# zeta2rework_lw_v36_ripup.net
KiCad netlist of a schematic drawn in EAGLE
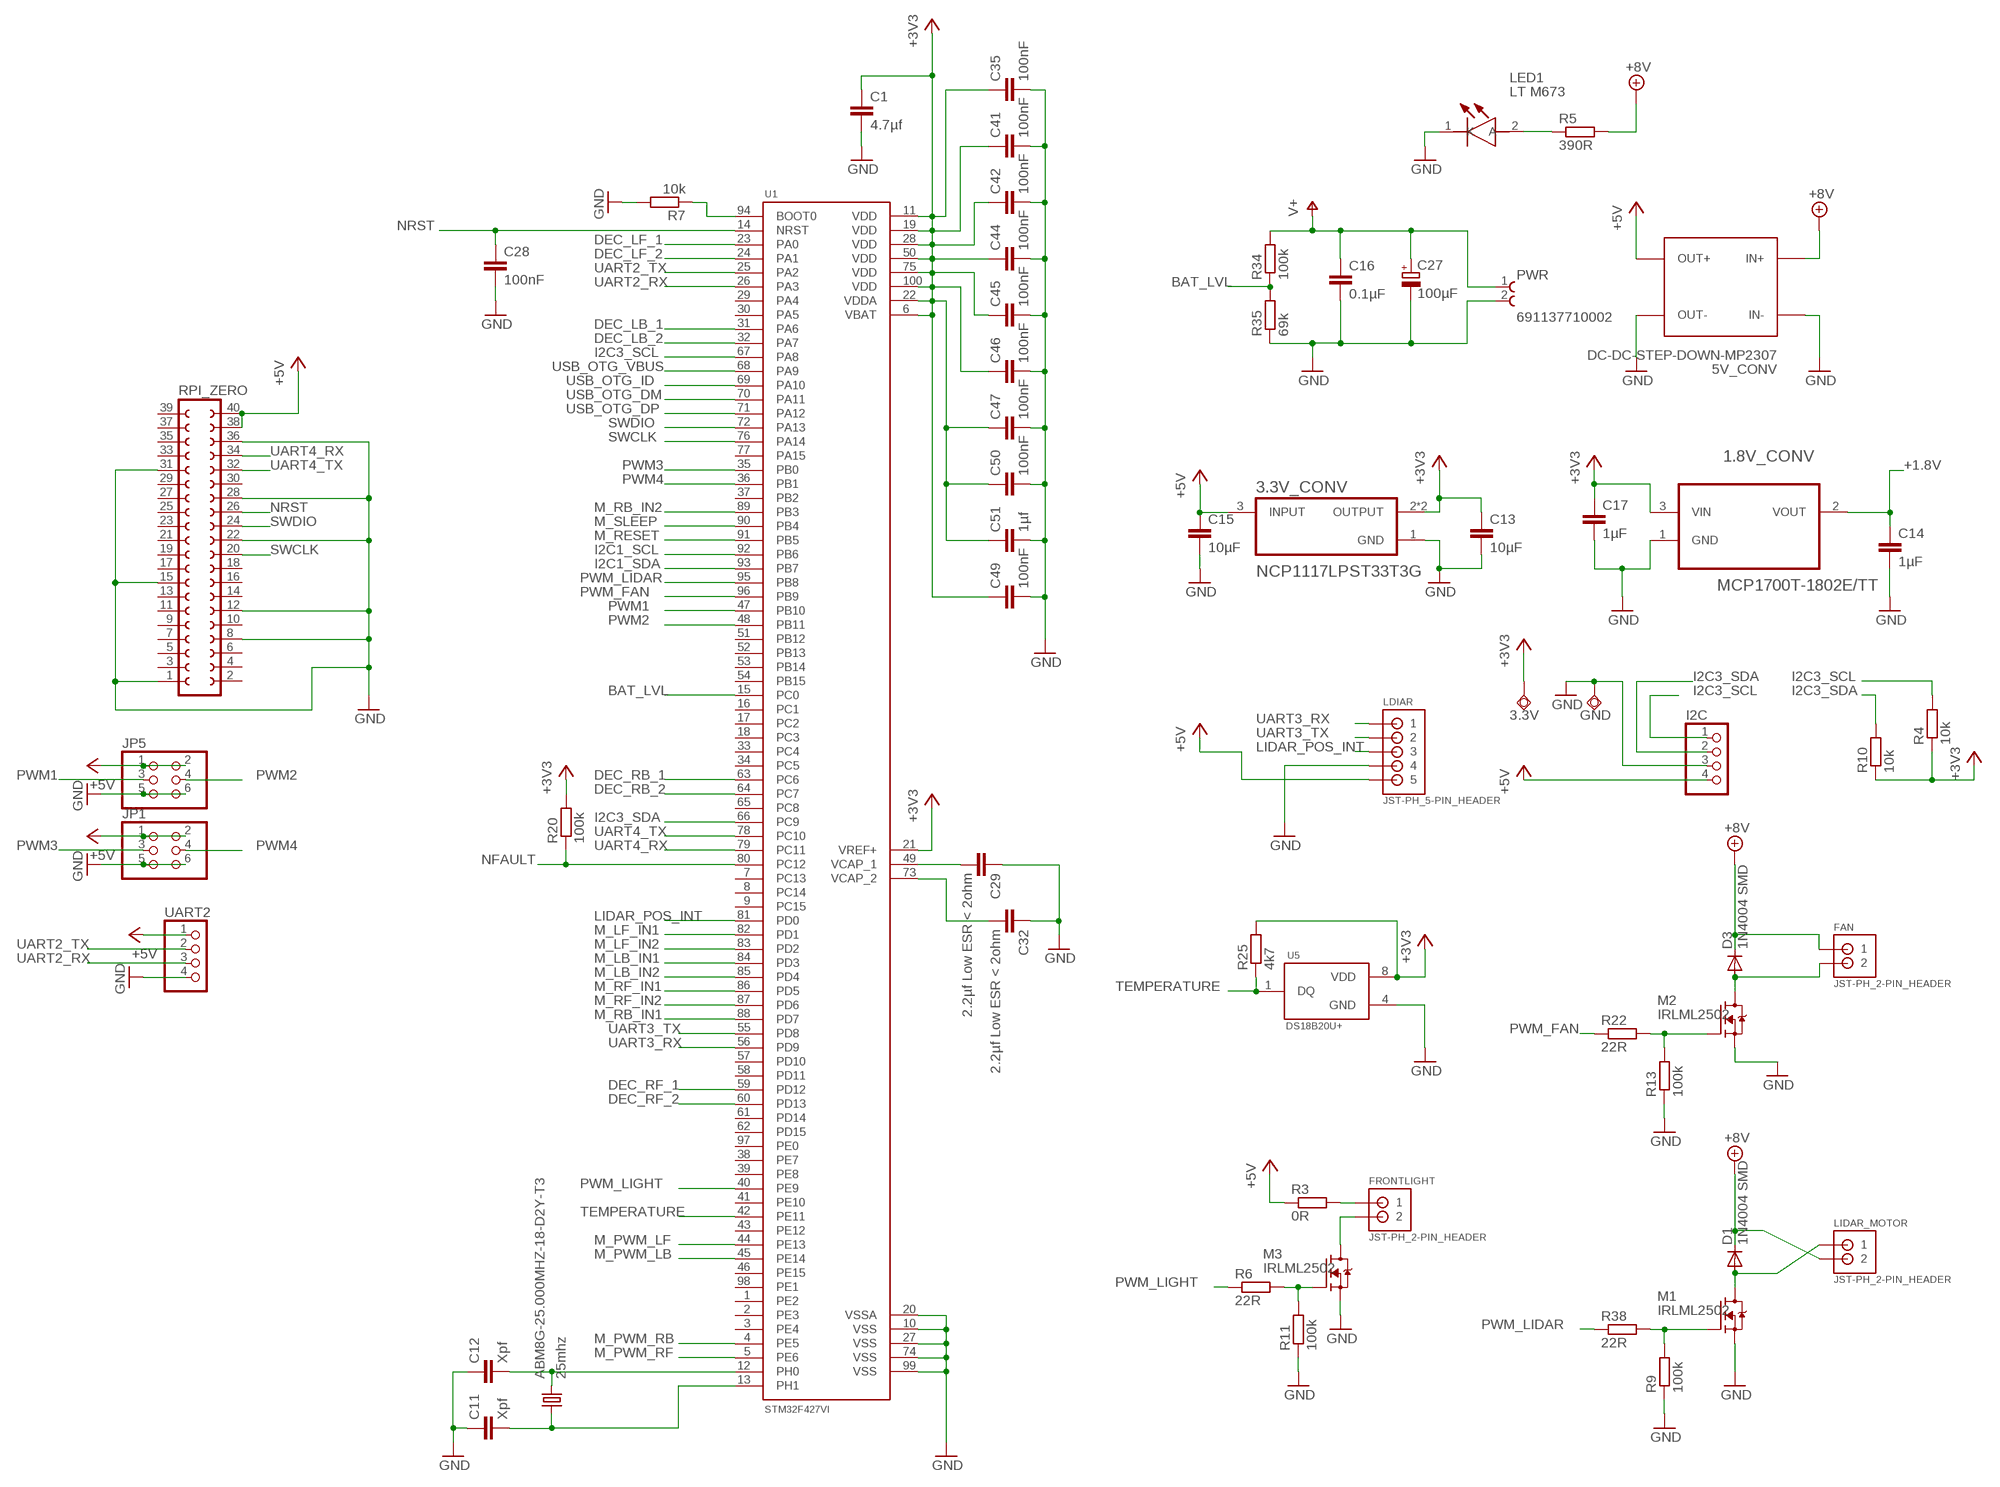
[diagram p0: schematic, sheet 1, part 1 of 2]
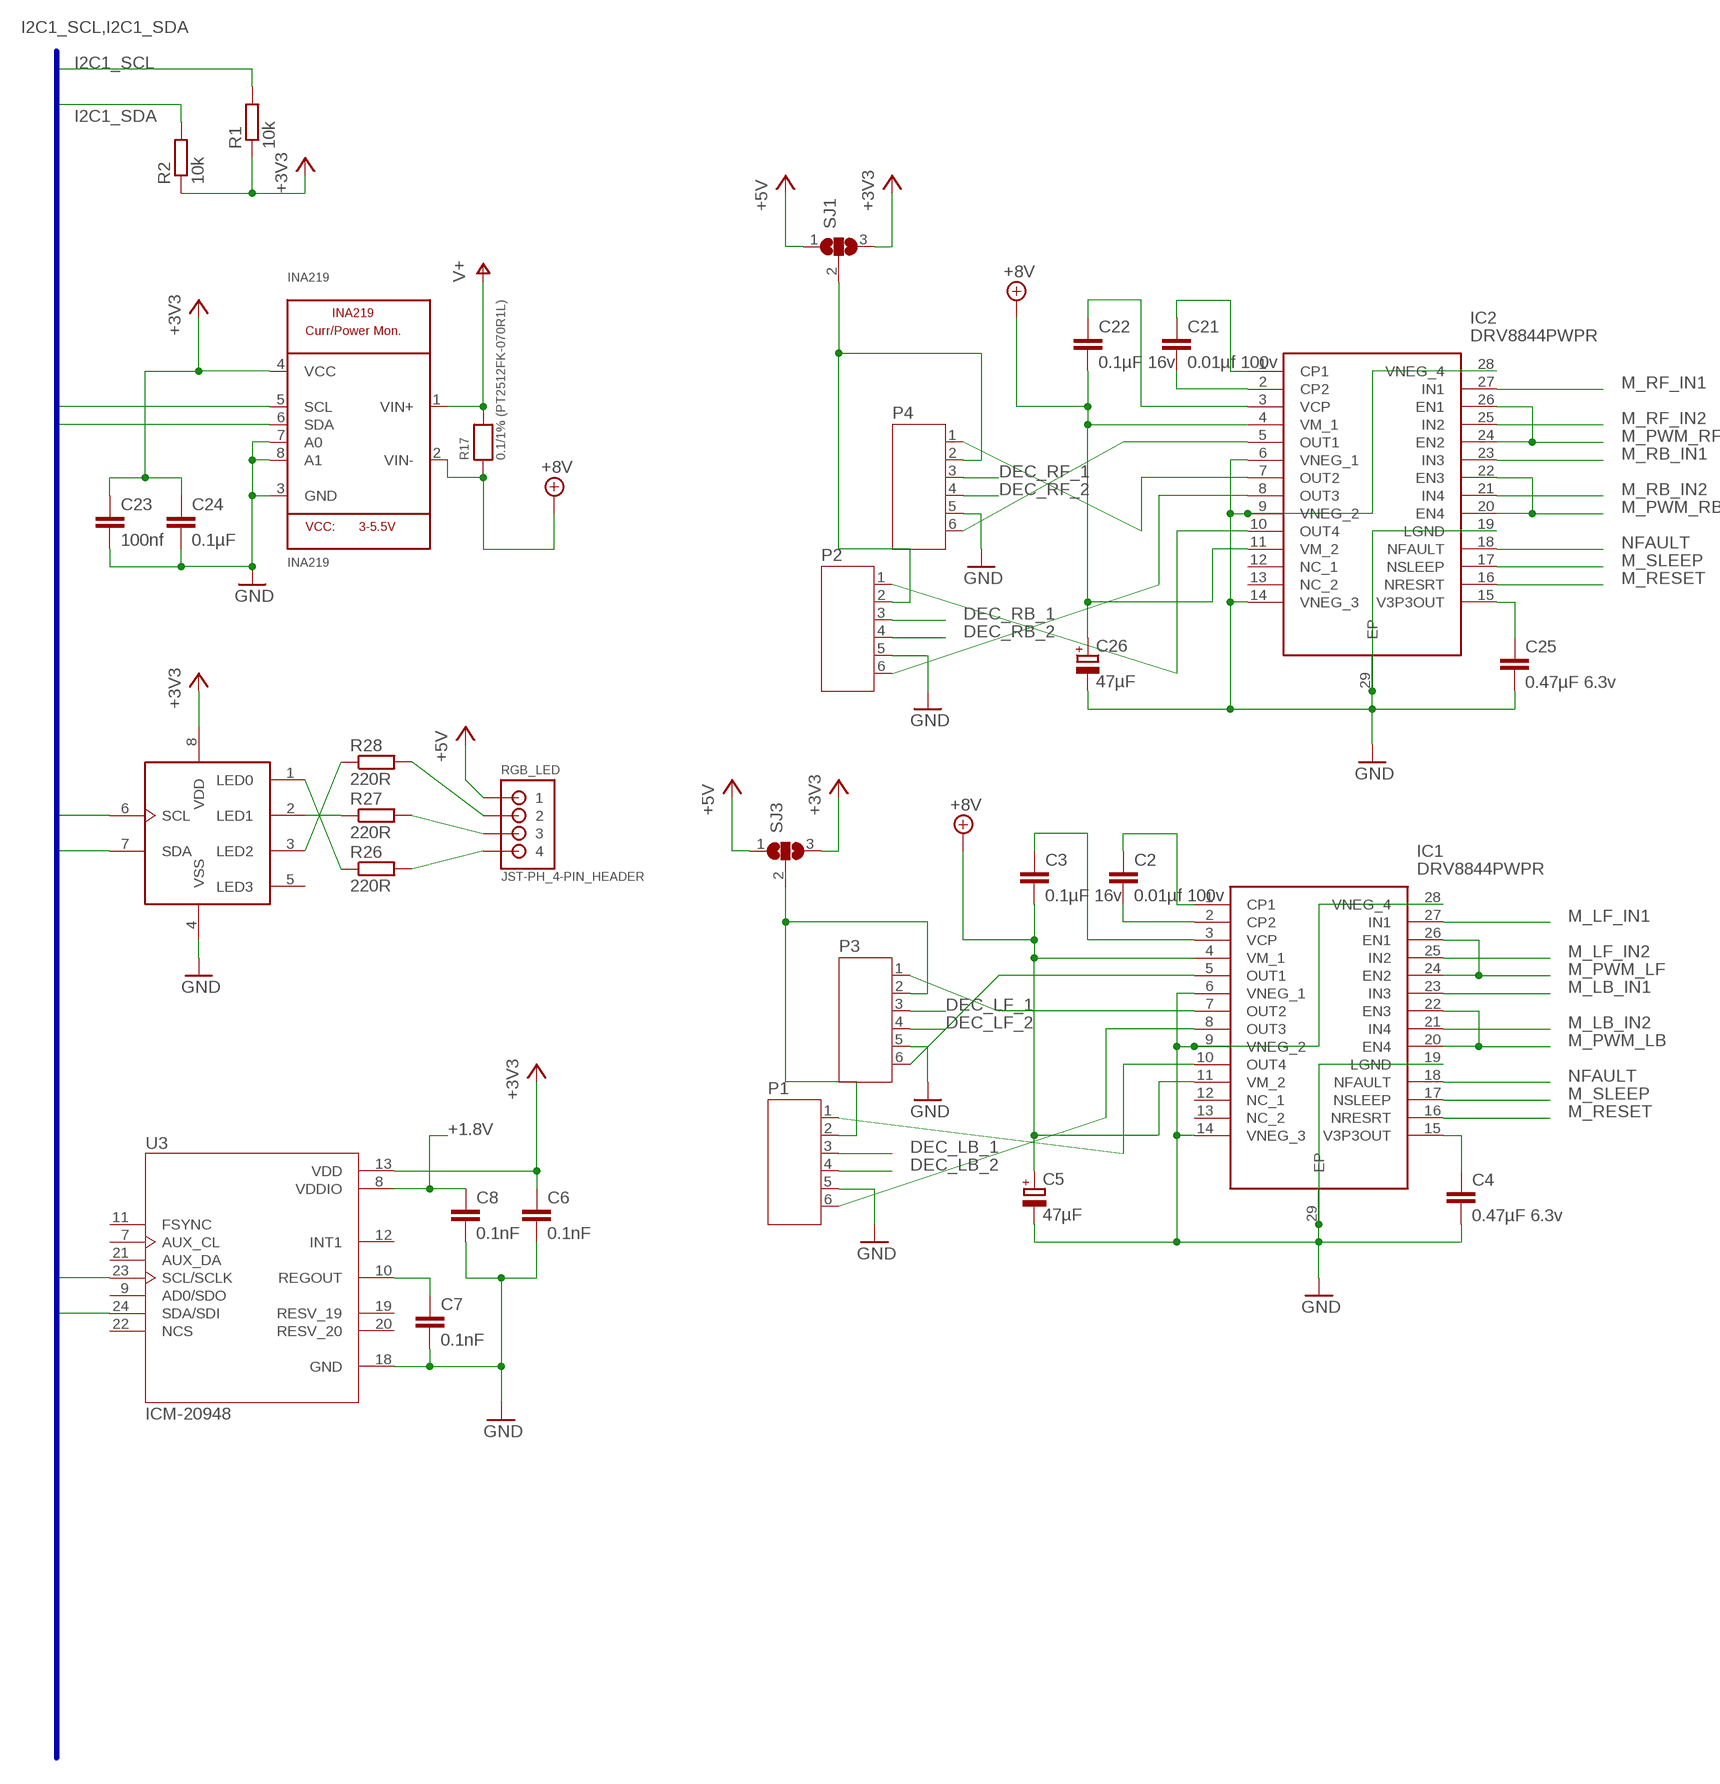
[diagram p1: schematic, sheet 1, part 2 of 2]

(export (version "E")
  (design (tool "Eeschema 10.0.6"))
  (components
    (comp (ref "1.8V_CONV")
      (value "MCP1700T-1802E/TT")
      (footprint "eagle-import:SOT95P237X112-3N")
      (fields (field (name "MF") "Microchip") (field (name "MP") "MCP1700T-2102E/TT"))
      (libsource (lib "eagle-import") (part "MCP1700T-2102E/TT"))
    )
    (comp (ref "3.3V")
      (value "TPSQTP20R")
      (footprint "eagle-import:TP20R")
      (libsource (lib "eagle-import") (part "TPSQTP20R"))
    )
    (comp (ref "3.3V_CONV")
      (value "NCP1117LPST33T3G")
      (footprint "eagle-import:SOT230P700X175-4N")
      (fields (field (name "MF") "ON Semiconductor"))
      (libsource (lib "eagle-import") (part "NCP1117LPST33T3G"))
    )
    (comp (ref "5V_CONV")
      (value "DC-DC-STEP-DOWN-MP2307")
      (footprint "eagle-import:DC-DC-STEP-DOWN-MP2307")
      (libsource (lib "eagle-import") (part "DC-DC-STEP-DOWN-MP2307"))
    )
    (comp (ref "ABM8G-25.000MHZ-18-D2Y-T3")
      (value "25mhz")
      (footprint "eagle-import:5.0X3.2_KX-9A")
      (libsource (lib "eagle-import") (part "KX-9A"))
    )
    (comp (ref "C1")
      (value "4.7µf")
      (footprint "eagle-import:C0603")
      (libsource (lib "eagle-import") (part "C-EUC0603"))
    )
    (comp (ref "C2")
      (value "0.01µf 100v")
      (footprint "eagle-import:C0603")
      (libsource (lib "eagle-import") (part "C-EUC0603"))
    )
    (comp (ref "C3")
      (value "0.1µF 16v")
      (footprint "eagle-import:C0603")
      (libsource (lib "eagle-import") (part "C-EUC0603"))
    )
    (comp (ref "C4")
      (value "0.47µF 6.3v")
      (footprint "eagle-import:C0603")
      (libsource (lib "eagle-import") (part "C-EUC0603"))
    )
    (comp (ref "C5")
      (value "47µF")
      (footprint "eagle-import:UD-5X5,8_NICHICON")
      (libsource (lib "eagle-import") (part "CPOL-EUUD-5X5,8"))
    )
    (comp (ref "C6")
      (value "0.1nF")
      (footprint "eagle-import:C0603")
      (libsource (lib "eagle-import") (part "C-EUC0603"))
    )
    (comp (ref "C7")
      (value "0.1nF")
      (footprint "eagle-import:C0603")
      (libsource (lib "eagle-import") (part "C-EUC0603"))
    )
    (comp (ref "C8")
      (value "0.1nF")
      (footprint "eagle-import:C0603")
      (libsource (lib "eagle-import") (part "C-EUC0603"))
    )
    (comp (ref "C11")
      (value "Xpf")
      (footprint "eagle-import:C0603")
      (libsource (lib "eagle-import") (part "C-EUC0603"))
    )
    (comp (ref "C12")
      (value "Xpf")
      (footprint "eagle-import:C0603")
      (libsource (lib "eagle-import") (part "C-EUC0603"))
    )
    (comp (ref "C13")
      (value "10µF")
      (footprint "eagle-import:C1206")
      (libsource (lib "eagle-import") (part "C-EUC1206"))
    )
    (comp (ref "C14")
      (value "1µF")
      (footprint "eagle-import:C0603")
      (libsource (lib "eagle-import") (part "C-EUC0603"))
    )
    (comp (ref "C15")
      (value "10µF")
      (footprint "eagle-import:C1206")
      (libsource (lib "eagle-import") (part "C-EUC1206"))
    )
    (comp (ref "C16")
      (value "0.1µF")
      (footprint "eagle-import:C0603")
      (libsource (lib "eagle-import") (part "C-EUC0603"))
    )
    (comp (ref "C17")
      (value "1µF")
      (footprint "eagle-import:C0603")
      (libsource (lib "eagle-import") (part "C-EUC0603"))
    )
    (comp (ref "C21")
      (value "0.01µf 100v")
      (footprint "eagle-import:C0603")
      (libsource (lib "eagle-import") (part "C-EUC0603"))
    )
    (comp (ref "C22")
      (value "0.1µF 16v")
      (footprint "eagle-import:C0603")
      (libsource (lib "eagle-import") (part "C-EUC0603"))
    )
    (comp (ref "C23")
      (value "100nf")
      (footprint "eagle-import:C0603")
      (libsource (lib "eagle-import") (part "C-EUC0603"))
    )
    (comp (ref "C24")
      (value "0.1µF")
      (footprint "eagle-import:C0603")
      (libsource (lib "eagle-import") (part "C-EUC0603"))
    )
    (comp (ref "C25")
      (value "0.47µF 6.3v")
      (footprint "eagle-import:C0603")
      (libsource (lib "eagle-import") (part "C-EUC0603"))
    )
    (comp (ref "C26")
      (value "47µF")
      (footprint "eagle-import:UD-5X5,8_NICHICON")
      (libsource (lib "eagle-import") (part "CPOL-EUUD-5X5,8"))
    )
    (comp (ref "C27")
      (value "100µF")
      (footprint "eagle-import:UD-5X5,8_NICHICON")
      (libsource (lib "eagle-import") (part "CPOL-EUUD-5X5,8"))
    )
    (comp (ref "C28")
      (value "100nF")
      (footprint "eagle-import:C0603")
      (libsource (lib "eagle-import") (part "C-EUC0603"))
    )
    (comp (ref "C29")
      (value "2.2µf Low ESR < 2ohm")
      (footprint "eagle-import:C1206")
      (libsource (lib "eagle-import") (part "C-EUC1206"))
    )
    (comp (ref "C32")
      (value "2.2µf Low ESR < 2ohm")
      (footprint "eagle-import:C1206")
      (libsource (lib "eagle-import") (part "C-EUC1206"))
    )
    (comp (ref "C35")
      (value "100nF")
      (footprint "eagle-import:C0603")
      (libsource (lib "eagle-import") (part "C-EUC0603"))
    )
    (comp (ref "C41")
      (value "100nF")
      (footprint "eagle-import:C0603")
      (libsource (lib "eagle-import") (part "C-EUC0603"))
    )
    (comp (ref "C42")
      (value "100nF")
      (footprint "eagle-import:C0603")
      (libsource (lib "eagle-import") (part "C-EUC0603"))
    )
    (comp (ref "C44")
      (value "100nF")
      (footprint "eagle-import:C0603")
      (libsource (lib "eagle-import") (part "C-EUC0603"))
    )
    (comp (ref "C45")
      (value "100nF")
      (footprint "eagle-import:C0603")
      (libsource (lib "eagle-import") (part "C-EUC0603"))
    )
    (comp (ref "C46")
      (value "100nF")
      (footprint "eagle-import:C0603")
      (libsource (lib "eagle-import") (part "C-EUC0603"))
    )
    (comp (ref "C47")
      (value "100nF")
      (footprint "eagle-import:C0603")
      (libsource (lib "eagle-import") (part "C-EUC0603"))
    )
    (comp (ref "C49")
      (value "100nF")
      (footprint "eagle-import:C0603")
      (libsource (lib "eagle-import") (part "C-EUC0603"))
    )
    (comp (ref "C50")
      (value "100nF")
      (footprint "eagle-import:C0603")
      (libsource (lib "eagle-import") (part "C-EUC0603"))
    )
    (comp (ref "C51")
      (value "1µf")
      (footprint "eagle-import:C0603")
      (libsource (lib "eagle-import") (part "C-EUC0603"))
    )
    (comp (ref "D1")
      (value "1N4004 SMD")
      (footprint "eagle-import:DO214AC")
      (libsource (lib "eagle-import") (part "DIODE-DO214AC"))
    )
    (comp (ref "D3")
      (value "1N4004 SMD")
      (footprint "eagle-import:DO214AC")
      (libsource (lib "eagle-import") (part "DIODE-DO214AC"))
    )
    (comp (ref "FAN")
      (value "JST-PH_2-PIN_HEADER")
      (footprint "eagle-import:JST_B2B-PH_HEADER")
      (libsource (lib "eagle-import") (part "JST-PH_2-PIN_HEADER"))
    )
    (comp (ref "FRONTLIGHT")
      (value "JST-PH_2-PIN_HEADER")
      (footprint "eagle-import:JST_B2B-PH_HEADER")
      (libsource (lib "eagle-import") (part "JST-PH_2-PIN_HEADER"))
    )
    (comp (ref "GND")
      (value "TPSQTP20R")
      (footprint "eagle-import:TP20R")
      (libsource (lib "eagle-import") (part "TPSQTP20R"))
    )
    (comp (ref "I2C")
      (value "PINHD-1X4")
      (footprint "eagle-import:1X04")
      (libsource (lib "eagle-import") (part "PINHD-1X4"))
    )
    (comp (ref "IC1")
      (value "DRV8844PWPR")
      (footprint "eagle-import:SOP65P640X120-29N")
      (fields (field (name "MOUSER_PART_NUMBER") "595-DRV8844PWPR"))
      (libsource (lib "eagle-import") (part "DRV8844PWPR"))
    )
    (comp (ref "IC2")
      (value "DRV8844PWPR")
      (footprint "eagle-import:SOP65P640X120-29N")
      (fields (field (name "MOUSER_PART_NUMBER") "595-DRV8844PWPR"))
      (libsource (lib "eagle-import") (part "DRV8844PWPR"))
    )
    (comp (ref "INA219")
      (value "INA219")
      (footprint "eagle-import:SOT23-8")
      (fields (field (name "MF") "Texas Instruments"))
      (libsource (lib "eagle-import") (part "INA219"))
    )
    (comp (ref "JP1")
      (value "PINHD-2X3")
      (footprint "eagle-import:2X03")
      (libsource (lib "eagle-import") (part "PINHD-2X3"))
    )
    (comp (ref "JP5")
      (value "PINHD-2X3")
      (footprint "eagle-import:2X03")
      (libsource (lib "eagle-import") (part "PINHD-2X3"))
    )
    (comp (ref "LDIAR")
      (value "JST-PH_5-PIN_HEADER")
      (footprint "eagle-import:JST_B5B-PH_HEADER")
      (libsource (lib "eagle-import") (part "JST-PH_5-PIN_HEADER"))
    )
    (comp (ref "LED1")
      (value "LT M673")
      (footprint "eagle-import:LTM673-N1R2-25")
      (fields
        (field (name "MANUFACTURER_PART_NUMBER") "LT M673-N1R2-25")
        (field (name "MOUSER_PART_NUMBER") "720-LTM673N1R225Z")
        (field (name "RS_PART_NUMBER") "9133231")
      )
      (libsource (lib "eagle-import") (part "LT_M673-N1R2-25"))
    )
    (comp (ref "LIDAR_MOTOR")
      (value "JST-PH_2-PIN_HEADER")
      (footprint "eagle-import:JST_B2B-PH_HEADER")
      (libsource (lib "eagle-import") (part "JST-PH_2-PIN_HEADER"))
    )
    (comp (ref "M1")
      (value "IRLML2502")
      (footprint "eagle-import:SOT23")
      (fields (field (name "MF") "Infineon") (field (name "MP") "IRLML2502TRPBF"))
      (libsource (lib "eagle-import") (part "IRLML2502TRPBF"))
    )
    (comp (ref "M2")
      (value "IRLML2502")
      (footprint "eagle-import:SOT23")
      (fields (field (name "MF") "Infineon") (field (name "MP") "IRLML2502TRPBF"))
      (libsource (lib "eagle-import") (part "IRLML2502TRPBF"))
    )
    (comp (ref "M3")
      (value "IRLML2502")
      (footprint "eagle-import:SOT23")
      (fields (field (name "MF") "Infineon") (field (name "MP") "IRLML2502TRPBF"))
      (libsource (lib "eagle-import") (part "IRLML2502TRPBF"))
    )
    (comp (ref "P1")
      (value "JST-PH6")
      (footprint "eagle-import:JST-PH6")
      (libsource (lib "eagle-import") (part "JST-PH6"))
    )
    (comp (ref "P2")
      (value "JST-PH6")
      (footprint "eagle-import:JST-PH6")
      (libsource (lib "eagle-import") (part "JST-PH6"))
    )
    (comp (ref "P3")
      (value "JST-PH6")
      (footprint "eagle-import:JST-PH6")
      (libsource (lib "eagle-import") (part "JST-PH6"))
    )
    (comp (ref "P4")
      (value "JST-PH6")
      (footprint "eagle-import:JST-PH6")
      (libsource (lib "eagle-import") (part "JST-PH6"))
    )
    (comp (ref "PCA9533")
      (value "PCA9533")
      (footprint "eagle-import:SOIC8")
      (libsource (lib "eagle-import") (part "PCA9533"))
    )
    (comp (ref "PWR")
      (value "691137710002")
      (footprint "eagle-import:691137710002")
      (fields (field (name "MF") "Wurth Electronics"))
      (libsource (lib "eagle-import") (part "691137710002"))
    )
    (comp (ref "R1")
      (value "10k")
      (footprint "eagle-import:R0603")
      (libsource (lib "eagle-import") (part "R-EU_R0603"))
    )
    (comp (ref "R2")
      (value "10k")
      (footprint "eagle-import:R0603")
      (libsource (lib "eagle-import") (part "R-EU_R0603"))
    )
    (comp (ref "R3")
      (value "0R")
      (footprint "eagle-import:R0603")
      (libsource (lib "eagle-import") (part "R-EU_R0603"))
    )
    (comp (ref "R4")
      (value "10k")
      (footprint "eagle-import:R0603")
      (libsource (lib "eagle-import") (part "R-EU_R0603"))
    )
    (comp (ref "R5")
      (value "390R")
      (footprint "eagle-import:R0603")
      (libsource (lib "eagle-import") (part "R-EU_R0603"))
    )
    (comp (ref "R6")
      (value "22R")
      (footprint "eagle-import:R0603")
      (libsource (lib "eagle-import") (part "R-EU_R0603"))
    )
    (comp (ref "R7")
      (value "10k")
      (footprint "eagle-import:R0603")
      (libsource (lib "eagle-import") (part "R-EU_R0603"))
    )
    (comp (ref "R9")
      (value "100k")
      (footprint "eagle-import:R0603")
      (libsource (lib "eagle-import") (part "R-EU_R0603"))
    )
    (comp (ref "R10")
      (value "10k")
      (footprint "eagle-import:R0603")
      (libsource (lib "eagle-import") (part "R-EU_R0603"))
    )
    (comp (ref "R11")
      (value "100k")
      (footprint "eagle-import:R0603")
      (libsource (lib "eagle-import") (part "R-EU_R0603"))
    )
    (comp (ref "R13")
      (value "100k")
      (footprint "eagle-import:R0603")
      (libsource (lib "eagle-import") (part "R-EU_R0603"))
    )
    (comp (ref "R17")
      (value "0.1/1% (PT2512FK-070R1L)")
      (footprint "eagle-import:2512")
      (libsource (lib "eagle-import") (part "RESISTOR2512"))
    )
    (comp (ref "R20")
      (value "100k")
      (footprint "eagle-import:R0603")
      (libsource (lib "eagle-import") (part "R-EU_R0603"))
    )
    (comp (ref "R22")
      (value "22R")
      (footprint "eagle-import:R0603")
      (libsource (lib "eagle-import") (part "R-EU_R0603"))
    )
    (comp (ref "R25")
      (value "4k7")
      (footprint "eagle-import:R0603")
      (libsource (lib "eagle-import") (part "R-EU_R0603"))
    )
    (comp (ref "R26")
      (value "220R")
      (footprint "eagle-import:R0603")
      (libsource (lib "eagle-import") (part "R-EU_R0603"))
    )
    (comp (ref "R27")
      (value "220R")
      (footprint "eagle-import:R0603")
      (libsource (lib "eagle-import") (part "R-EU_R0603"))
    )
    (comp (ref "R28")
      (value "220R")
      (footprint "eagle-import:R0603")
      (libsource (lib "eagle-import") (part "R-EU_R0603"))
    )
    (comp (ref "R34")
      (value "100k")
      (footprint "eagle-import:R0603")
      (libsource (lib "eagle-import") (part "R-EU_R0603"))
    )
    (comp (ref "R35")
      (value "69k")
      (footprint "eagle-import:R0603")
      (libsource (lib "eagle-import") (part "R-EU_R0603"))
    )
    (comp (ref "R38")
      (value "22R")
      (footprint "eagle-import:R0603")
      (libsource (lib "eagle-import") (part "R-EU_R0603"))
    )
    (comp (ref "RGB_LED")
      (value "JST-PH_4-PIN_HEADER")
      (footprint "eagle-import:JST_B4B-PH_HEADER")
      (libsource (lib "eagle-import") (part "JST-PH_4-PIN_HEADER"))
    )
    (comp (ref "RPI_ZERO")
      (value "FE20-2")
      (footprint "eagle-import:FE20-2")
      (libsource (lib "eagle-import") (part "FE20-2"))
    )
    (comp (ref "SJ1")
      (value "SJ2W")
      (footprint "eagle-import:SJ_2")
      (libsource (lib "eagle-import") (part "SJ2W"))
    )
    (comp (ref "SJ3")
      (value "SJ2W")
      (footprint "eagle-import:SJ_2")
      (libsource (lib "eagle-import") (part "SJ2W"))
    )
    (comp (ref "U1")
      (value "STM32F427VI")
      (footprint "eagle-import:QFP50P1600X1600X160-100N")
      (fields (field (name "MF") "STMicroelectronics") (field (name "MP") "STM32F427VGT7"))
      (libsource (lib "eagle-import") (part "STM32F427VGT7"))
    )
    (comp (ref "U3")
      (value "ICM-20948")
      (footprint "eagle-import:QFN40P300X300X105-25N")
      (fields (field (name "MF") "TDK InvenSense"))
      (libsource (lib "eagle-import") (part "ICM-20948"))
    )
    (comp (ref "U5")
      (value "DS18B20U+")
      (footprint "eagle-import:SOP65P490X95-8N")
      (fields (field (name "MF") "Maxim"))
      (libsource (lib "eagle-import") (part "DS18B20U+"))
    )
    (comp (ref "UART2")
      (value "PINHD-1X4")
      (footprint "eagle-import:1X04")
      (libsource (lib "eagle-import") (part "PINHD-1X4"))
    )
  )
  (nets
    (net (code "1") (name "+3V3") (class "Default")
      (node (ref "1.8V_CONV") (pin "3") (pinfunction "VIN_3") (pintype "input"))
      (node (ref "3.3V") (pin "TP") (pinfunction "TP_TP") (pintype "input"))
      (node (ref "3.3V_CONV") (pin "2") (pinfunction "OUTPUT_2") (pintype "output"))
      (node (ref "3.3V_CONV") (pin "4") (pinfunction "OUTPUT_4") (pintype "output"))
      (node (ref "C1") (pin "1") (pinfunction "1_1") (pintype "passive"))
      (node (ref "C13") (pin "1") (pinfunction "1_1") (pintype "passive"))
      (node (ref "C17") (pin "1") (pinfunction "1_1") (pintype "passive"))
      (node (ref "C23") (pin "1") (pinfunction "1_1") (pintype "passive"))
      (node (ref "C24") (pin "1") (pinfunction "1_1") (pintype "passive"))
      (node (ref "C35") (pin "1") (pinfunction "1_1") (pintype "passive"))
      (node (ref "C41") (pin "1") (pinfunction "1_1") (pintype "passive"))
      (node (ref "C42") (pin "1") (pinfunction "1_1") (pintype "passive"))
      (node (ref "C44") (pin "1") (pinfunction "1_1") (pintype "passive"))
      (node (ref "C45") (pin "1") (pinfunction "1_1") (pintype "passive"))
      (node (ref "C46") (pin "1") (pinfunction "1_1") (pintype "passive"))
      (node (ref "C47") (pin "1") (pinfunction "1_1") (pintype "passive"))
      (node (ref "C49") (pin "1") (pinfunction "1_1") (pintype "passive"))
      (node (ref "C50") (pin "1") (pinfunction "1_1") (pintype "passive"))
      (node (ref "C51") (pin "1") (pinfunction "1_1") (pintype "passive"))
      (node (ref "C6") (pin "1") (pinfunction "1_1") (pintype "passive"))
      (node (ref "INA219") (pin "4") (pinfunction "VCC_4") (pintype "bidirectional"))
      (node (ref "PCA9533") (pin "8") (pinfunction "VDD_8") (pintype "power_in"))
      (node (ref "R1") (pin "1") (pinfunction "1_1") (pintype "passive"))
      (node (ref "R10") (pin "1") (pinfunction "1_1") (pintype "passive"))
      (node (ref "R2") (pin "1") (pinfunction "1_1") (pintype "passive"))
      (node (ref "R20") (pin "2") (pinfunction "2_2") (pintype "passive"))
      (node (ref "R25") (pin "2") (pinfunction "2_2") (pintype "passive"))
      (node (ref "R4") (pin "1") (pinfunction "1_1") (pintype "passive"))
      (node (ref "SJ1") (pin "3") (pinfunction "3_3") (pintype "passive"))
      (node (ref "SJ3") (pin "3") (pinfunction "3_3") (pintype "passive"))
      (node (ref "U1") (pin "100") (pinfunction "VDD_100") (pintype "power_in"))
      (node (ref "U1") (pin "11") (pinfunction "VDD_11") (pintype "power_in"))
      (node (ref "U1") (pin "19") (pinfunction "VDD_19") (pintype "power_in"))
      (node (ref "U1") (pin "21") (pinfunction "VREF+_21") (pintype "power_in"))
      (node (ref "U1") (pin "22") (pinfunction "VDDA_22") (pintype "power_in"))
      (node (ref "U1") (pin "28") (pinfunction "VDD_28") (pintype "power_in"))
      (node (ref "U1") (pin "50") (pinfunction "VDD_50") (pintype "power_in"))
      (node (ref "U1") (pin "6") (pinfunction "VBAT_6") (pintype "power_in"))
      (node (ref "U1") (pin "75") (pinfunction "VDD_75") (pintype "power_in"))
      (node (ref "U3") (pin "13") (pinfunction "VDD_13") (pintype "power_in"))
      (node (ref "U5") (pin "8") (pinfunction "VDD_8") (pintype "power_in"))
    )
    (net (code "2") (name "+5V") (class "Default")
      (node (ref "3.3V_CONV") (pin "3") (pinfunction "INPUT_3") (pintype "input"))
      (node (ref "5V_CONV") (pin "OUT+") (pinfunction "OUT+_OUT+") (pintype "bidirectional"))
      (node (ref "C15") (pin "1") (pinfunction "1_1") (pintype "passive"))
      (node (ref "I2C") (pin "4") (pinfunction "4_4") (pintype "passive"))
      (node (ref "JP1") (pin "1") (pinfunction "1_1") (pintype "passive"))
      (node (ref "JP1") (pin "2") (pinfunction "2_2") (pintype "passive"))
      (node (ref "JP5") (pin "1") (pinfunction "1_1") (pintype "passive"))
      (node (ref "JP5") (pin "2") (pinfunction "2_2") (pintype "passive"))
      (node (ref "LDIAR") (pin "P5") (pinfunction "5_P5") (pintype "bidirectional"))
      (node (ref "R3") (pin "1") (pinfunction "1_1") (pintype "passive"))
      (node (ref "RGB_LED") (pin "P1") (pinfunction "1_P1") (pintype "bidirectional"))
      (node (ref "RPI_ZERO") (pin "38") (pinfunction "38_38") (pintype "passive"))
      (node (ref "RPI_ZERO") (pin "40") (pinfunction "40_40") (pintype "passive"))
      (node (ref "SJ1") (pin "1") (pinfunction "1_1") (pintype "passive"))
      (node (ref "SJ3") (pin "1") (pinfunction "1_1") (pintype "passive"))
      (node (ref "UART2") (pin "1") (pinfunction "1_1") (pintype "passive"))
    )
    (net (code "3") (name "+8V") (class "Default")
      (node (ref "5V_CONV") (pin "IN+") (pinfunction "IN+_IN+") (pintype "bidirectional"))
      (node (ref "C22") (pin "2") (pinfunction "2_2") (pintype "passive"))
      (node (ref "C26") (pin "+") (pinfunction "+_+") (pintype "passive"))
      (node (ref "C3") (pin "2") (pinfunction "2_2") (pintype "passive"))
      (node (ref "C5") (pin "+") (pinfunction "+_+") (pintype "passive"))
      (node (ref "D1") (pin "C") (pinfunction "C_C") (pintype "passive"))
      (node (ref "D3") (pin "C") (pinfunction "C_C") (pintype "passive"))
      (node (ref "FAN") (pin "P1") (pinfunction "1_P1") (pintype "bidirectional"))
      (node (ref "IC1") (pin "11") (pinfunction "VM_2_11") (pintype "bidirectional"))
      (node (ref "IC1") (pin "4") (pinfunction "VM_1_4") (pintype "bidirectional"))
      (node (ref "IC2") (pin "11") (pinfunction "VM_2_11") (pintype "bidirectional"))
      (node (ref "IC2") (pin "4") (pinfunction "VM_1_4") (pintype "bidirectional"))
      (node (ref "INA219") (pin "2") (pinfunction "VIN-_2") (pintype "bidirectional"))
      (node (ref "LIDAR_MOTOR") (pin "P2") (pinfunction "2_P2") (pintype "bidirectional"))
      (node (ref "R17") (pin "1") (pinfunction "1_1") (pintype "passive"))
      (node (ref "R5") (pin "2") (pinfunction "2_2") (pintype "passive"))
    )
    (net (code "4") (name "/+1.8V") (class "Default")
      (node (ref "1.8V_CONV") (pin "2") (pinfunction "VOUT_2") (pintype "output"))
      (node (ref "C14") (pin "1") (pinfunction "1_1") (pintype "passive"))
      (node (ref "C8") (pin "1") (pinfunction "1_1") (pintype "passive"))
      (node (ref "U3") (pin "8") (pinfunction "VDDIO_8") (pintype "power_in"))
    )
    (net (code "5") (name "/BAT_LVL") (class "Default")
      (node (ref "R34") (pin "1") (pinfunction "1_1") (pintype "passive"))
      (node (ref "R35") (pin "2") (pinfunction "2_2") (pintype "passive"))
      (node (ref "U1") (pin "15") (pinfunction "PC0_15") (pintype "bidirectional"))
    )
    (net (code "6") (name "/DEC_LB_1") (class "Default")
      (node (ref "P1") (pin "3") (pinfunction "3_3") (pintype "passive"))
      (node (ref "U1") (pin "31") (pinfunction "PA6_31") (pintype "bidirectional"))
    )
    (net (code "7") (name "/DEC_LB_2") (class "Default")
      (node (ref "P1") (pin "4") (pinfunction "4_4") (pintype "passive"))
      (node (ref "U1") (pin "32") (pinfunction "PA7_32") (pintype "bidirectional"))
    )
    (net (code "8") (name "/DEC_LF_1") (class "Default")
      (node (ref "P3") (pin "3") (pinfunction "3_3") (pintype "passive"))
      (node (ref "U1") (pin "23") (pinfunction "PA0_23") (pintype "bidirectional"))
    )
    (net (code "9") (name "/DEC_LF_2") (class "Default")
      (node (ref "P3") (pin "4") (pinfunction "4_4") (pintype "passive"))
      (node (ref "U1") (pin "24") (pinfunction "PA1_24") (pintype "bidirectional"))
    )
    (net (code "10") (name "/DEC_RB_1") (class "Default")
      (node (ref "P2") (pin "3") (pinfunction "3_3") (pintype "passive"))
      (node (ref "U1") (pin "63") (pinfunction "PC6_63") (pintype "bidirectional"))
    )
    (net (code "11") (name "/DEC_RB_2") (class "Default")
      (node (ref "P2") (pin "4") (pinfunction "4_4") (pintype "passive"))
      (node (ref "U1") (pin "64") (pinfunction "PC7_64") (pintype "bidirectional"))
    )
    (net (code "12") (name "/DEC_RF_1") (class "Default")
      (node (ref "P4") (pin "3") (pinfunction "3_3") (pintype "passive"))
      (node (ref "U1") (pin "59") (pinfunction "PD12_59") (pintype "bidirectional"))
    )
    (net (code "13") (name "/DEC_RF_2") (class "Default")
      (node (ref "P4") (pin "4") (pinfunction "4_4") (pintype "passive"))
      (node (ref "U1") (pin "60") (pinfunction "PD13_60") (pintype "bidirectional"))
    )
    (net (code "14") (name "/I2C1_SCL") (class "Default")
      (node (ref "INA219") (pin "5") (pinfunction "SCL_5") (pintype "bidirectional"))
      (node (ref "PCA9533") (pin "6") (pinfunction "SCL_6") (pintype "input"))
      (node (ref "R1") (pin "2") (pinfunction "2_2") (pintype "passive"))
      (node (ref "U1") (pin "92") (pinfunction "PB6_92") (pintype "bidirectional"))
      (node (ref "U3") (pin "23") (pinfunction "SCL/SCLK_23") (pintype "input"))
    )
    (net (code "15") (name "/I2C1_SDA") (class "Default")
      (node (ref "INA219") (pin "6") (pinfunction "SDA_6") (pintype "bidirectional"))
      (node (ref "PCA9533") (pin "7") (pinfunction "SDA_7") (pintype "bidirectional"))
      (node (ref "R2") (pin "2") (pinfunction "2_2") (pintype "passive"))
      (node (ref "U1") (pin "93") (pinfunction "PB7_93") (pintype "bidirectional"))
      (node (ref "U3") (pin "24") (pinfunction "SDA/SDI_24") (pintype "bidirectional"))
    )
    (net (code "16") (name "/I2C3_SCL") (class "Default")
      (node (ref "I2C") (pin "1") (pinfunction "1_1") (pintype "passive"))
      (node (ref "R4") (pin "2") (pinfunction "2_2") (pintype "passive"))
      (node (ref "U1") (pin "67") (pinfunction "PA8_67") (pintype "bidirectional"))
    )
    (net (code "17") (name "/I2C3_SDA") (class "Default")
      (node (ref "I2C") (pin "2") (pinfunction "2_2") (pintype "passive"))
      (node (ref "R10") (pin "2") (pinfunction "2_2") (pintype "passive"))
      (node (ref "U1") (pin "66") (pinfunction "PC9_66") (pintype "bidirectional"))
    )
    (net (code "18") (name "/LIDAR_POS_INT") (class "Default")
      (node (ref "LDIAR") (pin "P3") (pinfunction "3_P3") (pintype "bidirectional"))
      (node (ref "U1") (pin "81") (pinfunction "PD0_81") (pintype "bidirectional"))
    )
    (net (code "19") (name "/M_LB_IN1") (class "Default")
      (node (ref "IC1") (pin "23") (pinfunction "IN3_23") (pintype "input"))
      (node (ref "U1") (pin "84") (pinfunction "PD3_84") (pintype "bidirectional"))
    )
    (net (code "20") (name "/M_LB_IN2") (class "Default")
      (node (ref "IC1") (pin "21") (pinfunction "IN4_21") (pintype "input"))
      (node (ref "U1") (pin "85") (pinfunction "PD4_85") (pintype "bidirectional"))
    )
    (net (code "21") (name "/M_LF_IN1") (class "Default")
      (node (ref "IC1") (pin "27") (pinfunction "IN1_27") (pintype "input"))
      (node (ref "U1") (pin "82") (pinfunction "PD1_82") (pintype "bidirectional"))
    )
    (net (code "22") (name "/M_LF_IN2") (class "Default")
      (node (ref "IC1") (pin "25") (pinfunction "IN2_25") (pintype "input"))
      (node (ref "U1") (pin "83") (pinfunction "PD2_83") (pintype "bidirectional"))
    )
    (net (code "23") (name "/M_PWM_LB") (class "Default")
      (node (ref "IC1") (pin "20") (pinfunction "EN4_20") (pintype "bidirectional"))
      (node (ref "IC1") (pin "22") (pinfunction "EN3_22") (pintype "bidirectional"))
      (node (ref "U1") (pin "45") (pinfunction "PE14_45") (pintype "bidirectional"))
    )
    (net (code "24") (name "/M_PWM_LF") (class "Default")
      (node (ref "IC1") (pin "24") (pinfunction "EN2_24") (pintype "bidirectional"))
      (node (ref "IC1") (pin "26") (pinfunction "EN1_26") (pintype "bidirectional"))
      (node (ref "U1") (pin "44") (pinfunction "PE13_44") (pintype "bidirectional"))
    )
    (net (code "25") (name "/M_PWM_RB") (class "Default")
      (node (ref "IC2") (pin "20") (pinfunction "EN4_20") (pintype "bidirectional"))
      (node (ref "IC2") (pin "22") (pinfunction "EN3_22") (pintype "bidirectional"))
      (node (ref "U1") (pin "4") (pinfunction "PE5_4") (pintype "bidirectional"))
    )
    (net (code "26") (name "/M_PWM_RF") (class "Default")
      (node (ref "IC2") (pin "24") (pinfunction "EN2_24") (pintype "bidirectional"))
      (node (ref "IC2") (pin "26") (pinfunction "EN1_26") (pintype "bidirectional"))
      (node (ref "U1") (pin "5") (pinfunction "PE6_5") (pintype "bidirectional"))
    )
    (net (code "27") (name "/M_RB_IN1") (class "Default")
      (node (ref "IC2") (pin "23") (pinfunction "IN3_23") (pintype "input"))
      (node (ref "U1") (pin "88") (pinfunction "PD7_88") (pintype "bidirectional"))
    )
    (net (code "28") (name "/M_RB_IN2") (class "Default")
      (node (ref "IC2") (pin "21") (pinfunction "IN4_21") (pintype "input"))
      (node (ref "U1") (pin "89") (pinfunction "PB3_89") (pintype "bidirectional"))
    )
    (net (code "29") (name "/M_RESET") (class "Default")
      (node (ref "IC1") (pin "16") (pinfunction "NRESRT_16") (pintype "bidirectional"))
      (node (ref "IC2") (pin "16") (pinfunction "NRESRT_16") (pintype "bidirectional"))
      (node (ref "U1") (pin "91") (pinfunction "PB5_91") (pintype "bidirectional"))
    )
    (net (code "30") (name "/M_RF_IN1") (class "Default")
      (node (ref "IC2") (pin "27") (pinfunction "IN1_27") (pintype "input"))
      (node (ref "U1") (pin "86") (pinfunction "PD5_86") (pintype "bidirectional"))
    )
    (net (code "31") (name "/M_RF_IN2") (class "Default")
      (node (ref "IC2") (pin "25") (pinfunction "IN2_25") (pintype "input"))
      (node (ref "U1") (pin "87") (pinfunction "PD6_87") (pintype "bidirectional"))
    )
    (net (code "32") (name "/M_SLEEP") (class "Default")
      (node (ref "IC1") (pin "17") (pinfunction "NSLEEP_17") (pintype "bidirectional"))
      (node (ref "IC2") (pin "17") (pinfunction "NSLEEP_17") (pintype "bidirectional"))
      (node (ref "U1") (pin "90") (pinfunction "PB4_90") (pintype "bidirectional"))
    )
    (net (code "33") (name "/NFAULT") (class "Default")
      (node (ref "IC1") (pin "18") (pinfunction "NFAULT_18") (pintype "bidirectional"))
      (node (ref "IC2") (pin "18") (pinfunction "NFAULT_18") (pintype "bidirectional"))
      (node (ref "R20") (pin "1") (pinfunction "1_1") (pintype "passive"))
      (node (ref "U1") (pin "80") (pinfunction "PC12_80") (pintype "bidirectional"))
    )
    (net (code "34") (name "/NRST") (class "Default")
      (node (ref "C28") (pin "1") (pinfunction "1_1") (pintype "passive"))
      (node (ref "RPI_ZERO") (pin "26") (pinfunction "26_26") (pintype "passive"))
      (node (ref "U1") (pin "14") (pinfunction "NRST_14") (pintype "bidirectional"))
    )
    (net (code "35") (name "/PWM1") (class "Default")
      (node (ref "JP5") (pin "3") (pinfunction "3_3") (pintype "passive"))
      (node (ref "U1") (pin "47") (pinfunction "PB10_47") (pintype "bidirectional"))
    )
    (net (code "36") (name "/PWM2") (class "Default")
      (node (ref "JP5") (pin "4") (pinfunction "4_4") (pintype "passive"))
      (node (ref "U1") (pin "48") (pinfunction "PB11_48") (pintype "bidirectional"))
    )
    (net (code "37") (name "/PWM3") (class "Default")
      (node (ref "JP1") (pin "3") (pinfunction "3_3") (pintype "passive"))
      (node (ref "U1") (pin "35") (pinfunction "PB0_35") (pintype "bidirectional"))
    )
    (net (code "38") (name "/PWM4") (class "Default")
      (node (ref "JP1") (pin "4") (pinfunction "4_4") (pintype "passive"))
      (node (ref "U1") (pin "36") (pinfunction "PB1_36") (pintype "bidirectional"))
    )
    (net (code "39") (name "/PWM_FAN") (class "Default")
      (node (ref "R22") (pin "1") (pinfunction "1_1") (pintype "passive"))
      (node (ref "U1") (pin "96") (pinfunction "PB9_96") (pintype "bidirectional"))
    )
    (net (code "40") (name "/PWM_LIDAR") (class "Default")
      (node (ref "R38") (pin "1") (pinfunction "1_1") (pintype "passive"))
      (node (ref "U1") (pin "95") (pinfunction "PB8_95") (pintype "bidirectional"))
    )
    (net (code "41") (name "/PWM_LIGHT") (class "Default")
      (node (ref "R6") (pin "1") (pinfunction "1_1") (pintype "passive"))
      (node (ref "U1") (pin "40") (pinfunction "PE9_40") (pintype "bidirectional"))
    )
    (net (code "42") (name "/SWCLK") (class "Default")
      (node (ref "RPI_ZERO") (pin "20") (pinfunction "20_20") (pintype "passive"))
      (node (ref "U1") (pin "76") (pinfunction "PA14_76") (pintype "bidirectional"))
    )
    (net (code "43") (name "/SWDIO") (class "Default")
      (node (ref "RPI_ZERO") (pin "24") (pinfunction "24_24") (pintype "passive"))
      (node (ref "U1") (pin "72") (pinfunction "PA13_72") (pintype "bidirectional"))
    )
    (net (code "44") (name "/TEMPERATURE") (class "Default")
      (node (ref "R25") (pin "1") (pinfunction "1_1") (pintype "passive"))
      (node (ref "U1") (pin "42") (pinfunction "PE11_42") (pintype "bidirectional"))
      (node (ref "U5") (pin "1") (pinfunction "DQ_1") (pintype "bidirectional"))
    )
    (net (code "45") (name "/UART2_RX") (class "Default")
      (node (ref "U1") (pin "26") (pinfunction "PA3_26") (pintype "bidirectional"))
      (node (ref "UART2") (pin "3") (pinfunction "3_3") (pintype "passive"))
    )
    (net (code "46") (name "/UART2_TX") (class "Default")
      (node (ref "U1") (pin "25") (pinfunction "PA2_25") (pintype "bidirectional"))
      (node (ref "UART2") (pin "2") (pinfunction "2_2") (pintype "passive"))
    )
    (net (code "47") (name "/UART3_RX") (class "Default")
      (node (ref "LDIAR") (pin "P1") (pinfunction "1_P1") (pintype "bidirectional"))
      (node (ref "U1") (pin "56") (pinfunction "PD9_56") (pintype "bidirectional"))
    )
    (net (code "48") (name "/UART3_TX") (class "Default")
      (node (ref "LDIAR") (pin "P2") (pinfunction "2_P2") (pintype "bidirectional"))
      (node (ref "U1") (pin "55") (pinfunction "PD8_55") (pintype "bidirectional"))
    )
    (net (code "49") (name "/UART4_RX") (class "Default")
      (node (ref "RPI_ZERO") (pin "34") (pinfunction "34_34") (pintype "passive"))
      (node (ref "U1") (pin "79") (pinfunction "PC11_79") (pintype "bidirectional"))
    )
    (net (code "50") (name "/UART4_TX") (class "Default")
      (node (ref "RPI_ZERO") (pin "32") (pinfunction "32_32") (pintype "passive"))
      (node (ref "U1") (pin "78") (pinfunction "PC10_78") (pintype "bidirectional"))
    )
    (net (code "51") (name "/USB_OTG_DM") (class "Default")
      (node (ref "U1") (pin "70") (pinfunction "PA11_70") (pintype "bidirectional"))
    )
    (net (code "52") (name "/USB_OTG_DP") (class "Default")
      (node (ref "U1") (pin "71") (pinfunction "PA12_71") (pintype "bidirectional"))
    )
    (net (code "53") (name "/USB_OTG_ID") (class "Default")
      (node (ref "U1") (pin "69") (pinfunction "PA10_69") (pintype "bidirectional"))
    )
    (net (code "54") (name "/USB_OTG_VBUS") (class "Default")
      (node (ref "U1") (pin "68") (pinfunction "PA9_68") (pintype "bidirectional"))
    )
    (net (code "56") (name "GND") (class "Default")
      (node (ref "1.8V_CONV") (pin "1") (pinfunction "GND_1") (pintype "passive"))
      (node (ref "3.3V_CONV") (pin "1") (pinfunction "GND_1") (pintype "power_in"))
      (node (ref "5V_CONV") (pin "IN-") (pinfunction "IN-_IN-") (pintype "bidirectional"))
      (node (ref "5V_CONV") (pin "OUT-") (pinfunction "OUT-_OUT-") (pintype "bidirectional"))
      (node (ref "C1") (pin "2") (pinfunction "2_2") (pintype "passive"))
      (node (ref "C11") (pin "1") (pinfunction "1_1") (pintype "passive"))
      (node (ref "C12") (pin "1") (pinfunction "1_1") (pintype "passive"))
      (node (ref "C13") (pin "2") (pinfunction "2_2") (pintype "passive"))
      (node (ref "C14") (pin "2") (pinfunction "2_2") (pintype "passive"))
      (node (ref "C15") (pin "2") (pinfunction "2_2") (pintype "passive"))
      (node (ref "C16") (pin "2") (pinfunction "2_2") (pintype "passive"))
      (node (ref "C17") (pin "2") (pinfunction "2_2") (pintype "passive"))
      (node (ref "C23") (pin "2") (pinfunction "2_2") (pintype "passive"))
      (node (ref "C24") (pin "2") (pinfunction "2_2") (pintype "passive"))
      (node (ref "C25") (pin "2") (pinfunction "2_2") (pintype "passive"))
      (node (ref "C26") (pin "-") (pinfunction "-_-") (pintype "passive"))
      (node (ref "C27") (pin "-") (pinfunction "-_-") (pintype "passive"))
      (node (ref "C28") (pin "2") (pinfunction "2_2") (pintype "passive"))
      (node (ref "C29") (pin "1") (pinfunction "1_1") (pintype "passive"))
      (node (ref "C32") (pin "1") (pinfunction "1_1") (pintype "passive"))
      (node (ref "C35") (pin "2") (pinfunction "2_2") (pintype "passive"))
      (node (ref "C4") (pin "2") (pinfunction "2_2") (pintype "passive"))
      (node (ref "C41") (pin "2") (pinfunction "2_2") (pintype "passive"))
      (node (ref "C42") (pin "2") (pinfunction "2_2") (pintype "passive"))
      (node (ref "C44") (pin "2") (pinfunction "2_2") (pintype "passive"))
      (node (ref "C45") (pin "2") (pinfunction "2_2") (pintype "passive"))
      (node (ref "C46") (pin "2") (pinfunction "2_2") (pintype "passive"))
      (node (ref "C47") (pin "2") (pinfunction "2_2") (pintype "passive"))
      (node (ref "C49") (pin "2") (pinfunction "2_2") (pintype "passive"))
      (node (ref "C5") (pin "-") (pinfunction "-_-") (pintype "passive"))
      (node (ref "C50") (pin "2") (pinfunction "2_2") (pintype "passive"))
      (node (ref "C51") (pin "2") (pinfunction "2_2") (pintype "passive"))
      (node (ref "C6") (pin "2") (pinfunction "2_2") (pintype "passive"))
      (node (ref "C7") (pin "2") (pinfunction "2_2") (pintype "passive"))
      (node (ref "C8") (pin "2") (pinfunction "2_2") (pintype "passive"))
      (node (ref "GND") (pin "TP") (pinfunction "TP_TP") (pintype "input"))
      (node (ref "I2C") (pin "3") (pinfunction "3_3") (pintype "passive"))
      (node (ref "IC1") (pin "14") (pinfunction "VNEG_3_14") (pintype "bidirectional"))
      (node (ref "IC1") (pin "19") (pinfunction "LGND_19") (pintype "power_in"))
      (node (ref "IC1") (pin "28") (pinfunction "VNEG_4_28") (pintype "bidirectional"))
      (node (ref "IC1") (pin "29") (pinfunction "EP_29") (pintype "power_in"))
      (node (ref "IC1") (pin "6") (pinfunction "VNEG_1_6") (pintype "bidirectional"))
      (node (ref "IC1") (pin "9") (pinfunction "VNEG_2_9") (pintype "bidirectional"))
      (node (ref "IC2") (pin "14") (pinfunction "VNEG_3_14") (pintype "bidirectional"))
      (node (ref "IC2") (pin "19") (pinfunction "LGND_19") (pintype "power_in"))
      (node (ref "IC2") (pin "28") (pinfunction "VNEG_4_28") (pintype "bidirectional"))
      (node (ref "IC2") (pin "29") (pinfunction "EP_29") (pintype "power_in"))
      (node (ref "IC2") (pin "6") (pinfunction "VNEG_1_6") (pintype "bidirectional"))
      (node (ref "IC2") (pin "9") (pinfunction "VNEG_2_9") (pintype "bidirectional"))
      (node (ref "INA219") (pin "3") (pinfunction "GND_3") (pintype "bidirectional"))
      (node (ref "INA219") (pin "7") (pinfunction "A0_7") (pintype "bidirectional"))
      (node (ref "INA219") (pin "8") (pinfunction "A1_8") (pintype "bidirectional"))
      (node (ref "JP1") (pin "5") (pinfunction "5_5") (pintype "passive"))
      (node (ref "JP1") (pin "6") (pinfunction "6_6") (pintype "passive"))
      (node (ref "JP5") (pin "5") (pinfunction "5_5") (pintype "passive"))
      (node (ref "JP5") (pin "6") (pinfunction "6_6") (pintype "passive"))
      (node (ref "LDIAR") (pin "P4") (pinfunction "4_P4") (pintype "bidirectional"))
      (node (ref "LED1") (pin "1") (pinfunction "K_1") (pintype "bidirectional"))
      (node (ref "M1") (pin "2") (pinfunction "S_2") (pintype "passive"))
      (node (ref "M2") (pin "2") (pinfunction "S_2") (pintype "passive"))
      (node (ref "M3") (pin "2") (pinfunction "S_2") (pintype "passive"))
      (node (ref "P1") (pin "5") (pinfunction "5_5") (pintype "passive"))
      (node (ref "P2") (pin "5") (pinfunction "5_5") (pintype "passive"))
      (node (ref "P3") (pin "5") (pinfunction "5_5") (pintype "passive"))
      (node (ref "P4") (pin "5") (pinfunction "5_5") (pintype "passive"))
      (node (ref "PCA9533") (pin "4") (pinfunction "VSS_4") (pintype "power_in"))
      (node (ref "PWR") (pin "2") (pinfunction "2_2") (pintype "passive"))
      (node (ref "R11") (pin "1") (pinfunction "1_1") (pintype "passive"))
      (node (ref "R13") (pin "1") (pinfunction "1_1") (pintype "passive"))
      (node (ref "R35") (pin "1") (pinfunction "1_1") (pintype "passive"))
      (node (ref "R7") (pin "2") (pinfunction "2_2") (pintype "passive"))
      (node (ref "R9") (pin "1") (pinfunction "1_1") (pintype "passive"))
      (node (ref "RPI_ZERO") (pin "1") (pinfunction "1_1") (pintype "passive"))
      (node (ref "RPI_ZERO") (pin "12") (pinfunction "12_12") (pintype "passive"))
      (node (ref "RPI_ZERO") (pin "15") (pinfunction "15_15") (pintype "passive"))
      (node (ref "RPI_ZERO") (pin "22") (pinfunction "22_22") (pintype "passive"))
      (node (ref "RPI_ZERO") (pin "28") (pinfunction "28_28") (pintype "passive"))
      (node (ref "RPI_ZERO") (pin "31") (pinfunction "31_31") (pintype "passive"))
      (node (ref "RPI_ZERO") (pin "36") (pinfunction "36_36") (pintype "passive"))
      (node (ref "RPI_ZERO") (pin "8") (pinfunction "8_8") (pintype "passive"))
      (node (ref "U1") (pin "10") (pinfunction "VSS_10") (pintype "power_in"))
      (node (ref "U1") (pin "20") (pinfunction "VSSA_20") (pintype "power_in"))
      (node (ref "U1") (pin "27") (pinfunction "VSS_27") (pintype "power_in"))
      (node (ref "U1") (pin "74") (pinfunction "VSS_74") (pintype "power_in"))
      (node (ref "U1") (pin "99") (pinfunction "VSS_99") (pintype "power_in"))
      (node (ref "U3") (pin "18") (pinfunction "GND_18") (pintype "power_in"))
      (node (ref "U5") (pin "4") (pinfunction "GND_4") (pintype "power_in"))
      (node (ref "UART2") (pin "4") (pinfunction "4_4") (pintype "passive"))
    )
    (net (code "57") (name "Net-(ABM8G-25.000MHZ-18-D2Y-T3-2)") (class "Default")
      (node (ref "ABM8G-25.000MHZ-18-D2Y-T3") (pin "3") (pinfunction "2_3") (pintype "passive"))
      (node (ref "C12") (pin "2") (pinfunction "2_2") (pintype "passive"))
      (node (ref "U1") (pin "12") (pinfunction "PH0_12") (pintype "bidirectional"))
    )
    (net (code "58") (name "Net-(FAN-2)") (class "Default")
      (node (ref "D3") (pin "A") (pinfunction "A_A") (pintype "passive"))
      (node (ref "FAN") (pin "P2") (pinfunction "2_P2") (pintype "bidirectional"))
      (node (ref "M2") (pin "3") (pinfunction "D_3") (pintype "passive"))
    )
    (net (code "59") (name "Net-(FRONTLIGHT-1)") (class "Default")
      (node (ref "FRONTLIGHT") (pin "P1") (pinfunction "1_P1") (pintype "bidirectional"))
      (node (ref "R3") (pin "2") (pinfunction "2_2") (pintype "passive"))
    )
    (net (code "60") (name "Net-(FRONTLIGHT-2)") (class "Default")
      (node (ref "FRONTLIGHT") (pin "P2") (pinfunction "2_P2") (pintype "bidirectional"))
      (node (ref "M3") (pin "3") (pinfunction "D_3") (pintype "passive"))
    )
    (net (code "61") (name "Net-(IC1-CP1)") (class "Default")
      (node (ref "C2") (pin "1") (pinfunction "1_1") (pintype "passive"))
      (node (ref "IC1") (pin "1") (pinfunction "CP1_1") (pintype "bidirectional"))
    )
    (net (code "62") (name "Net-(IC1-CP2)") (class "Default")
      (node (ref "C2") (pin "2") (pinfunction "2_2") (pintype "passive"))
      (node (ref "IC1") (pin "2") (pinfunction "CP2_2") (pintype "bidirectional"))
    )
    (net (code "63") (name "Net-(IC1-OUT1)") (class "Default")
      (node (ref "IC1") (pin "5") (pinfunction "OUT1_5") (pintype "output"))
      (node (ref "P3") (pin "6") (pinfunction "6_6") (pintype "passive"))
    )
    (net (code "64") (name "Net-(IC1-OUT2)") (class "Default")
      (node (ref "IC1") (pin "7") (pinfunction "OUT2_7") (pintype "output"))
      (node (ref "P3") (pin "1") (pinfunction "1_1") (pintype "passive"))
    )
    (net (code "65") (name "Net-(IC1-OUT3)") (class "Default")
      (node (ref "IC1") (pin "8") (pinfunction "OUT3_8") (pintype "output"))
      (node (ref "P1") (pin "6") (pinfunction "6_6") (pintype "passive"))
    )
    (net (code "66") (name "Net-(IC1-OUT4)") (class "Default")
      (node (ref "IC1") (pin "10") (pinfunction "OUT4_10") (pintype "output"))
      (node (ref "P1") (pin "1") (pinfunction "1_1") (pintype "passive"))
    )
    (net (code "67") (name "Net-(IC1-V3P3OUT)") (class "Default")
      (node (ref "C4") (pin "1") (pinfunction "1_1") (pintype "passive"))
      (node (ref "IC1") (pin "15") (pinfunction "V3P3OUT_15") (pintype "output"))
    )
    (net (code "68") (name "Net-(IC1-VCP)") (class "Default")
      (node (ref "C3") (pin "1") (pinfunction "1_1") (pintype "passive"))
      (node (ref "IC1") (pin "3") (pinfunction "VCP_3") (pintype "bidirectional"))
    )
    (net (code "69") (name "Net-(IC2-CP1)") (class "Default")
      (node (ref "C21") (pin "1") (pinfunction "1_1") (pintype "passive"))
      (node (ref "IC2") (pin "1") (pinfunction "CP1_1") (pintype "bidirectional"))
    )
    (net (code "70") (name "Net-(IC2-CP2)") (class "Default")
      (node (ref "C21") (pin "2") (pinfunction "2_2") (pintype "passive"))
      (node (ref "IC2") (pin "2") (pinfunction "CP2_2") (pintype "bidirectional"))
    )
    (net (code "71") (name "Net-(IC2-OUT1)") (class "Default")
      (node (ref "IC2") (pin "5") (pinfunction "OUT1_5") (pintype "output"))
      (node (ref "P4") (pin "6") (pinfunction "6_6") (pintype "passive"))
    )
    (net (code "72") (name "Net-(IC2-OUT2)") (class "Default")
      (node (ref "IC2") (pin "7") (pinfunction "OUT2_7") (pintype "output"))
      (node (ref "P4") (pin "1") (pinfunction "1_1") (pintype "passive"))
    )
    (net (code "73") (name "Net-(IC2-OUT3)") (class "Default")
      (node (ref "IC2") (pin "8") (pinfunction "OUT3_8") (pintype "output"))
      (node (ref "P2") (pin "6") (pinfunction "6_6") (pintype "passive"))
    )
    (net (code "74") (name "Net-(IC2-OUT4)") (class "Default")
      (node (ref "IC2") (pin "10") (pinfunction "OUT4_10") (pintype "output"))
      (node (ref "P2") (pin "1") (pinfunction "1_1") (pintype "passive"))
    )
    (net (code "75") (name "Net-(IC2-V3P3OUT)") (class "Default")
      (node (ref "C25") (pin "1") (pinfunction "1_1") (pintype "passive"))
      (node (ref "IC2") (pin "15") (pinfunction "V3P3OUT_15") (pintype "output"))
    )
    (net (code "76") (name "Net-(IC2-VCP)") (class "Default")
      (node (ref "C22") (pin "1") (pinfunction "1_1") (pintype "passive"))
      (node (ref "IC2") (pin "3") (pinfunction "VCP_3") (pintype "bidirectional"))
    )
    (net (code "77") (name "Net-(LED1-A)") (class "Default")
      (node (ref "LED1") (pin "2") (pinfunction "A_2") (pintype "bidirectional"))
      (node (ref "R5") (pin "1") (pinfunction "1_1") (pintype "passive"))
    )
    (net (code "78") (name "Net-(LIDAR_MOTOR-1)") (class "Default")
      (node (ref "D1") (pin "A") (pinfunction "A_A") (pintype "passive"))
      (node (ref "LIDAR_MOTOR") (pin "P1") (pinfunction "1_P1") (pintype "bidirectional"))
      (node (ref "M1") (pin "3") (pinfunction "D_3") (pintype "passive"))
    )
    (net (code "79") (name "Net-(M1-G)") (class "Default")
      (node (ref "M1") (pin "1") (pinfunction "G_1") (pintype "passive"))
      (node (ref "R38") (pin "2") (pinfunction "2_2") (pintype "passive"))
      (node (ref "R9") (pin "2") (pinfunction "2_2") (pintype "passive"))
    )
    (net (code "80") (name "Net-(M2-G)") (class "Default")
      (node (ref "M2") (pin "1") (pinfunction "G_1") (pintype "passive"))
      (node (ref "R13") (pin "2") (pinfunction "2_2") (pintype "passive"))
      (node (ref "R22") (pin "2") (pinfunction "2_2") (pintype "passive"))
    )
    (net (code "81") (name "Net-(M3-G)") (class "Default")
      (node (ref "M3") (pin "1") (pinfunction "G_1") (pintype "passive"))
      (node (ref "R11") (pin "2") (pinfunction "2_2") (pintype "passive"))
      (node (ref "R6") (pin "2") (pinfunction "2_2") (pintype "passive"))
    )
    (net (code "82") (name "Net-(P1-Pad2)") (class "Default")
      (node (ref "P1") (pin "2") (pinfunction "2_2") (pintype "passive"))
      (node (ref "P3") (pin "2") (pinfunction "2_2") (pintype "passive"))
      (node (ref "SJ3") (pin "2") (pinfunction "2_2") (pintype "passive"))
    )
    (net (code "83") (name "Net-(P2-Pad2)") (class "Default")
      (node (ref "P2") (pin "2") (pinfunction "2_2") (pintype "passive"))
      (node (ref "P4") (pin "2") (pinfunction "2_2") (pintype "passive"))
      (node (ref "SJ1") (pin "2") (pinfunction "2_2") (pintype "passive"))
    )
    (net (code "84") (name "Net-(PCA9533-LED0)") (class "Default")
      (node (ref "PCA9533") (pin "1") (pinfunction "LED0_1") (pintype "bidirectional"))
      (node (ref "R26") (pin "1") (pinfunction "1_1") (pintype "passive"))
    )
    (net (code "85") (name "Net-(PCA9533-LED1)") (class "Default")
      (node (ref "PCA9533") (pin "2") (pinfunction "LED1_2") (pintype "bidirectional"))
      (node (ref "R27") (pin "1") (pinfunction "1_1") (pintype "passive"))
    )
    (net (code "86") (name "Net-(PCA9533-LED2)") (class "Default")
      (node (ref "PCA9533") (pin "3") (pinfunction "LED2_3") (pintype "bidirectional"))
      (node (ref "R28") (pin "1") (pinfunction "1_1") (pintype "passive"))
    )
    (net (code "87") (name "Net-(RGB_LED-2)") (class "Default")
      (node (ref "R28") (pin "2") (pinfunction "2_2") (pintype "passive"))
      (node (ref "RGB_LED") (pin "P2") (pinfunction "2_P2") (pintype "bidirectional"))
    )
    (net (code "88") (name "Net-(RGB_LED-3)") (class "Default")
      (node (ref "R27") (pin "2") (pinfunction "2_2") (pintype "passive"))
      (node (ref "RGB_LED") (pin "P3") (pinfunction "3_P3") (pintype "bidirectional"))
    )
    (net (code "89") (name "Net-(RGB_LED-4)") (class "Default")
      (node (ref "R26") (pin "2") (pinfunction "2_2") (pintype "passive"))
      (node (ref "RGB_LED") (pin "P4") (pinfunction "4_P4") (pintype "bidirectional"))
    )
    (net (code "90") (name "Net-(U1-BOOT0)") (class "Default")
      (node (ref "R7") (pin "1") (pinfunction "1_1") (pintype "passive"))
      (node (ref "U1") (pin "94") (pinfunction "BOOT0_94") (pintype "input"))
    )
    (net (code "91") (name "Net-(U1-PH1)") (class "Default")
      (node (ref "ABM8G-25.000MHZ-18-D2Y-T3") (pin "1") (pinfunction "1_1") (pintype "passive"))
      (node (ref "C11") (pin "2") (pinfunction "2_2") (pintype "passive"))
      (node (ref "U1") (pin "13") (pinfunction "PH1_13") (pintype "bidirectional"))
    )
    (net (code "92") (name "Net-(U1-VCAP_1)") (class "Default")
      (node (ref "C29") (pin "2") (pinfunction "2_2") (pintype "passive"))
      (node (ref "U1") (pin "49") (pinfunction "VCAP_1_49") (pintype "power_in"))
    )
    (net (code "93") (name "Net-(U1-VCAP_2)") (class "Default")
      (node (ref "C32") (pin "2") (pinfunction "2_2") (pintype "passive"))
      (node (ref "U1") (pin "73") (pinfunction "VCAP_2_73") (pintype "power_in"))
    )
    (net (code "94") (name "Net-(U3-REGOUT)") (class "Default")
      (node (ref "C7") (pin "1") (pinfunction "1_1") (pintype "passive"))
      (node (ref "U3") (pin "10") (pinfunction "REGOUT_10") (pintype "output"))
    )
    (net (code "95") (name "V+") (class "Default")
      (node (ref "C16") (pin "1") (pinfunction "1_1") (pintype "passive"))
      (node (ref "C27") (pin "+") (pinfunction "+_+") (pintype "passive"))
      (node (ref "INA219") (pin "1") (pinfunction "VIN+_1") (pintype "bidirectional"))
      (node (ref "PWR") (pin "1") (pinfunction "1_1") (pintype "passive"))
      (node (ref "R17") (pin "2") (pinfunction "2_2") (pintype "passive"))
      (node (ref "R34") (pin "2") (pinfunction "2_2") (pintype "passive"))
    )
    (net (code "96") (name "unconnected-(IC1-NC_1-Pad12)") (class "Default")
      (node (ref "IC1") (pin "12") (pinfunction "NC_1_12") (pintype "bidirectional"))
    )
    (net (code "97") (name "unconnected-(IC1-NC_2-Pad13)") (class "Default")
      (node (ref "IC1") (pin "13") (pinfunction "NC_2_13") (pintype "bidirectional"))
    )
    (net (code "98") (name "unconnected-(IC2-NC_1-Pad12)") (class "Default")
      (node (ref "IC2") (pin "12") (pinfunction "NC_1_12") (pintype "bidirectional"))
    )
    (net (code "99") (name "unconnected-(IC2-NC_2-Pad13)") (class "Default")
      (node (ref "IC2") (pin "13") (pinfunction "NC_2_13") (pintype "bidirectional"))
    )
    (net (code "100") (name "unconnected-(PCA9533-LED3-Pad5)") (class "Default")
      (node (ref "PCA9533") (pin "5") (pinfunction "LED3_5") (pintype "bidirectional"))
    )
    (net (code "101") (name "unconnected-(RPI_ZERO-Pad2)") (class "Default")
      (node (ref "RPI_ZERO") (pin "2") (pinfunction "2_2") (pintype "passive"))
    )
    (net (code "102") (name "unconnected-(RPI_ZERO-Pad3)") (class "Default")
      (node (ref "RPI_ZERO") (pin "3") (pinfunction "3_3") (pintype "passive"))
    )
    (net (code "103") (name "unconnected-(RPI_ZERO-Pad4)") (class "Default")
      (node (ref "RPI_ZERO") (pin "4") (pinfunction "4_4") (pintype "passive"))
    )
    (net (code "104") (name "unconnected-(RPI_ZERO-Pad5)") (class "Default")
      (node (ref "RPI_ZERO") (pin "5") (pinfunction "5_5") (pintype "passive"))
    )
    (net (code "105") (name "unconnected-(RPI_ZERO-Pad6)") (class "Default")
      (node (ref "RPI_ZERO") (pin "6") (pinfunction "6_6") (pintype "passive"))
    )
    (net (code "106") (name "unconnected-(RPI_ZERO-Pad7)") (class "Default")
      (node (ref "RPI_ZERO") (pin "7") (pinfunction "7_7") (pintype "passive"))
    )
    (net (code "107") (name "unconnected-(RPI_ZERO-Pad9)") (class "Default")
      (node (ref "RPI_ZERO") (pin "9") (pinfunction "9_9") (pintype "passive"))
    )
    (net (code "108") (name "unconnected-(RPI_ZERO-Pad10)") (class "Default")
      (node (ref "RPI_ZERO") (pin "10") (pinfunction "10_10") (pintype "passive"))
    )
    (net (code "109") (name "unconnected-(RPI_ZERO-Pad11)") (class "Default")
      (node (ref "RPI_ZERO") (pin "11") (pinfunction "11_11") (pintype "passive"))
    )
    (net (code "110") (name "unconnected-(RPI_ZERO-Pad13)") (class "Default")
      (node (ref "RPI_ZERO") (pin "13") (pinfunction "13_13") (pintype "passive"))
    )
    (net (code "111") (name "unconnected-(RPI_ZERO-Pad14)") (class "Default")
      (node (ref "RPI_ZERO") (pin "14") (pinfunction "14_14") (pintype "passive"))
    )
    (net (code "112") (name "unconnected-(RPI_ZERO-Pad16)") (class "Default")
      (node (ref "RPI_ZERO") (pin "16") (pinfunction "16_16") (pintype "passive"))
    )
    (net (code "113") (name "unconnected-(RPI_ZERO-Pad17)") (class "Default")
      (node (ref "RPI_ZERO") (pin "17") (pinfunction "17_17") (pintype "passive"))
    )
    (net (code "114") (name "unconnected-(RPI_ZERO-Pad18)") (class "Default")
      (node (ref "RPI_ZERO") (pin "18") (pinfunction "18_18") (pintype "passive"))
    )
    (net (code "115") (name "unconnected-(RPI_ZERO-Pad19)") (class "Default")
      (node (ref "RPI_ZERO") (pin "19") (pinfunction "19_19") (pintype "passive"))
    )
    (net (code "116") (name "unconnected-(RPI_ZERO-Pad21)") (class "Default")
      (node (ref "RPI_ZERO") (pin "21") (pinfunction "21_21") (pintype "passive"))
    )
    (net (code "117") (name "unconnected-(RPI_ZERO-Pad23)") (class "Default")
      (node (ref "RPI_ZERO") (pin "23") (pinfunction "23_23") (pintype "passive"))
    )
    (net (code "118") (name "unconnected-(RPI_ZERO-Pad25)") (class "Default")
      (node (ref "RPI_ZERO") (pin "25") (pinfunction "25_25") (pintype "passive"))
    )
    (net (code "119") (name "unconnected-(RPI_ZERO-Pad27)") (class "Default")
      (node (ref "RPI_ZERO") (pin "27") (pinfunction "27_27") (pintype "passive"))
    )
    (net (code "120") (name "unconnected-(RPI_ZERO-Pad29)") (class "Default")
      (node (ref "RPI_ZERO") (pin "29") (pinfunction "29_29") (pintype "passive"))
    )
    (net (code "121") (name "unconnected-(RPI_ZERO-Pad30)") (class "Default")
      (node (ref "RPI_ZERO") (pin "30") (pinfunction "30_30") (pintype "passive"))
    )
    (net (code "122") (name "unconnected-(RPI_ZERO-Pad33)") (class "Default")
      (node (ref "RPI_ZERO") (pin "33") (pinfunction "33_33") (pintype "passive"))
    )
    (net (code "123") (name "unconnected-(RPI_ZERO-Pad35)") (class "Default")
      (node (ref "RPI_ZERO") (pin "35") (pinfunction "35_35") (pintype "passive"))
    )
    (net (code "124") (name "unconnected-(RPI_ZERO-Pad37)") (class "Default")
      (node (ref "RPI_ZERO") (pin "37") (pinfunction "37_37") (pintype "passive"))
    )
    (net (code "125") (name "unconnected-(RPI_ZERO-Pad39)") (class "Default")
      (node (ref "RPI_ZERO") (pin "39") (pinfunction "39_39") (pintype "passive"))
    )
    (net (code "126") (name "unconnected-(U1-PA4-Pad29)") (class "Default")
      (node (ref "U1") (pin "29") (pinfunction "PA4_29") (pintype "bidirectional"))
    )
    (net (code "127") (name "unconnected-(U1-PA5-Pad30)") (class "Default")
      (node (ref "U1") (pin "30") (pinfunction "PA5_30") (pintype "bidirectional"))
    )
    (net (code "128") (name "unconnected-(U1-PA15-Pad77)") (class "Default")
      (node (ref "U1") (pin "77") (pinfunction "PA15_77") (pintype "bidirectional"))
    )
    (net (code "129") (name "unconnected-(U1-PB2-Pad37)") (class "Default")
      (node (ref "U1") (pin "37") (pinfunction "PB2_37") (pintype "bidirectional"))
    )
    (net (code "130") (name "unconnected-(U1-PB12-Pad51)") (class "Default")
      (node (ref "U1") (pin "51") (pinfunction "PB12_51") (pintype "bidirectional"))
    )
    (net (code "131") (name "unconnected-(U1-PB13-Pad52)") (class "Default")
      (node (ref "U1") (pin "52") (pinfunction "PB13_52") (pintype "bidirectional"))
    )
    (net (code "132") (name "unconnected-(U1-PB14-Pad53)") (class "Default")
      (node (ref "U1") (pin "53") (pinfunction "PB14_53") (pintype "bidirectional"))
    )
    (net (code "133") (name "unconnected-(U1-PB15-Pad54)") (class "Default")
      (node (ref "U1") (pin "54") (pinfunction "PB15_54") (pintype "bidirectional"))
    )
    (net (code "134") (name "unconnected-(U1-PC1-Pad16)") (class "Default")
      (node (ref "U1") (pin "16") (pinfunction "PC1_16") (pintype "bidirectional"))
    )
    (net (code "135") (name "unconnected-(U1-PC2-Pad17)") (class "Default")
      (node (ref "U1") (pin "17") (pinfunction "PC2_17") (pintype "bidirectional"))
    )
    (net (code "136") (name "unconnected-(U1-PC3-Pad18)") (class "Default")
      (node (ref "U1") (pin "18") (pinfunction "PC3_18") (pintype "bidirectional"))
    )
    (net (code "137") (name "unconnected-(U1-PC4-Pad33)") (class "Default")
      (node (ref "U1") (pin "33") (pinfunction "PC4_33") (pintype "bidirectional"))
    )
    (net (code "138") (name "unconnected-(U1-PC5-Pad34)") (class "Default")
      (node (ref "U1") (pin "34") (pinfunction "PC5_34") (pintype "bidirectional"))
    )
    (net (code "139") (name "unconnected-(U1-PC8-Pad65)") (class "Default")
      (node (ref "U1") (pin "65") (pinfunction "PC8_65") (pintype "bidirectional"))
    )
    (net (code "140") (name "unconnected-(U1-PC13-Pad7)") (class "Default")
      (node (ref "U1") (pin "7") (pinfunction "PC13_7") (pintype "bidirectional"))
    )
    (net (code "141") (name "unconnected-(U1-PC14-Pad8)") (class "Default")
      (node (ref "U1") (pin "8") (pinfunction "PC14_8") (pintype "bidirectional"))
    )
    (net (code "142") (name "unconnected-(U1-PC15-Pad9)") (class "Default")
      (node (ref "U1") (pin "9") (pinfunction "PC15_9") (pintype "bidirectional"))
    )
    (net (code "143") (name "unconnected-(U1-PD10-Pad57)") (class "Default")
      (node (ref "U1") (pin "57") (pinfunction "PD10_57") (pintype "bidirectional"))
    )
    (net (code "144") (name "unconnected-(U1-PD11-Pad58)") (class "Default")
      (node (ref "U1") (pin "58") (pinfunction "PD11_58") (pintype "bidirectional"))
    )
    (net (code "145") (name "unconnected-(U1-PD14-Pad61)") (class "Default")
      (node (ref "U1") (pin "61") (pinfunction "PD14_61") (pintype "bidirectional"))
    )
    (net (code "146") (name "unconnected-(U1-PD15-Pad62)") (class "Default")
      (node (ref "U1") (pin "62") (pinfunction "PD15_62") (pintype "bidirectional"))
    )
    (net (code "147") (name "unconnected-(U1-PE0-Pad97)") (class "Default")
      (node (ref "U1") (pin "97") (pinfunction "PE0_97") (pintype "bidirectional"))
    )
    (net (code "148") (name "unconnected-(U1-PE1-Pad98)") (class "Default")
      (node (ref "U1") (pin "98") (pinfunction "PE1_98") (pintype "bidirectional"))
    )
    (net (code "149") (name "unconnected-(U1-PE2-Pad1)") (class "Default")
      (node (ref "U1") (pin "1") (pinfunction "PE2_1") (pintype "bidirectional"))
    )
    (net (code "150") (name "unconnected-(U1-PE3-Pad2)") (class "Default")
      (node (ref "U1") (pin "2") (pinfunction "PE3_2") (pintype "bidirectional"))
    )
    (net (code "151") (name "unconnected-(U1-PE4-Pad3)") (class "Default")
      (node (ref "U1") (pin "3") (pinfunction "PE4_3") (pintype "bidirectional"))
    )
    (net (code "152") (name "unconnected-(U1-PE7-Pad38)") (class "Default")
      (node (ref "U1") (pin "38") (pinfunction "PE7_38") (pintype "bidirectional"))
    )
    (net (code "153") (name "unconnected-(U1-PE8-Pad39)") (class "Default")
      (node (ref "U1") (pin "39") (pinfunction "PE8_39") (pintype "bidirectional"))
    )
    (net (code "154") (name "unconnected-(U1-PE10-Pad41)") (class "Default")
      (node (ref "U1") (pin "41") (pinfunction "PE10_41") (pintype "bidirectional"))
    )
    (net (code "155") (name "unconnected-(U1-PE12-Pad43)") (class "Default")
      (node (ref "U1") (pin "43") (pinfunction "PE12_43") (pintype "bidirectional"))
    )
    (net (code "156") (name "unconnected-(U1-PE15-Pad46)") (class "Default")
      (node (ref "U1") (pin "46") (pinfunction "PE15_46") (pintype "bidirectional"))
    )
    (net (code "157") (name "unconnected-(U3-AD0{slash}SDO-Pad9)") (class "Default")
      (node (ref "U3") (pin "9") (pinfunction "AD0/SDO_9") (pintype "output"))
    )
    (net (code "158") (name "unconnected-(U3-AUX_CL-Pad7)") (class "Default")
      (node (ref "U3") (pin "7") (pinfunction "AUX_CL_7") (pintype "input"))
    )
    (net (code "159") (name "unconnected-(U3-AUX_DA-Pad21)") (class "Default")
      (node (ref "U3") (pin "21") (pinfunction "AUX_DA_21") (pintype "input"))
    )
    (net (code "160") (name "unconnected-(U3-FSYNC-Pad11)") (class "Default")
      (node (ref "U3") (pin "11") (pinfunction "FSYNC_11") (pintype "input"))
    )
    (net (code "161") (name "unconnected-(U3-INT1-Pad12)") (class "Default")
      (node (ref "U3") (pin "12") (pinfunction "INT1_12") (pintype "output"))
    )
    (net (code "162") (name "unconnected-(U3-NCS-Pad22)") (class "Default")
      (node (ref "U3") (pin "22") (pinfunction "NCS_22") (pintype "input"))
    )
    (net (code "163") (name "unconnected-(U3-RESV_19-Pad19)") (class "Default")
      (node (ref "U3") (pin "19") (pinfunction "RESV_19_19") (pintype "passive"))
    )
    (net (code "164") (name "unconnected-(U3-RESV_20-Pad20)") (class "Default")
      (node (ref "U3") (pin "20") (pinfunction "RESV_20_20") (pintype "passive"))
    )
  )
)
